# OMD_LEDS.net
KiCad netlist of a schematic drawn in Altium Designer
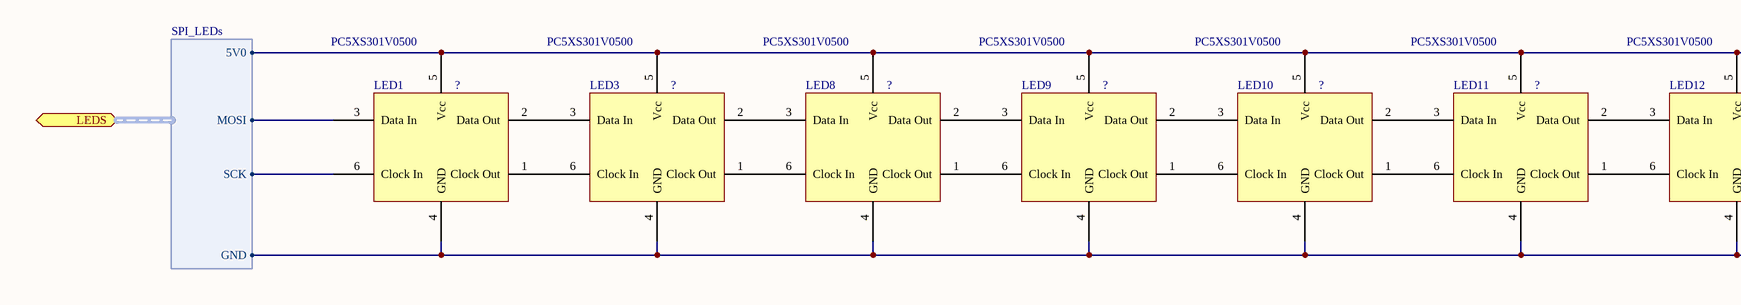
[diagram p0: OMD_LEDS.SchDoc, left]
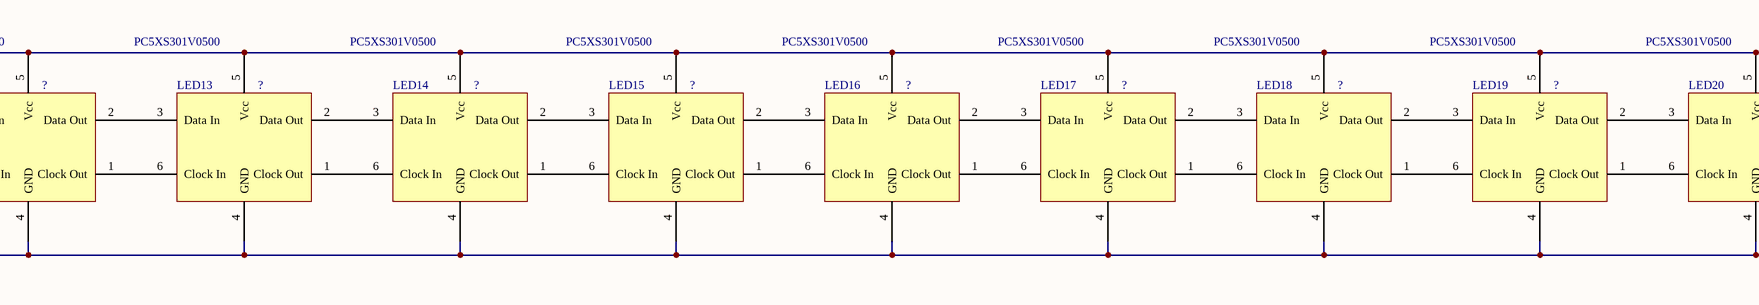
[diagram p1: OMD_LEDS.SchDoc, middle]
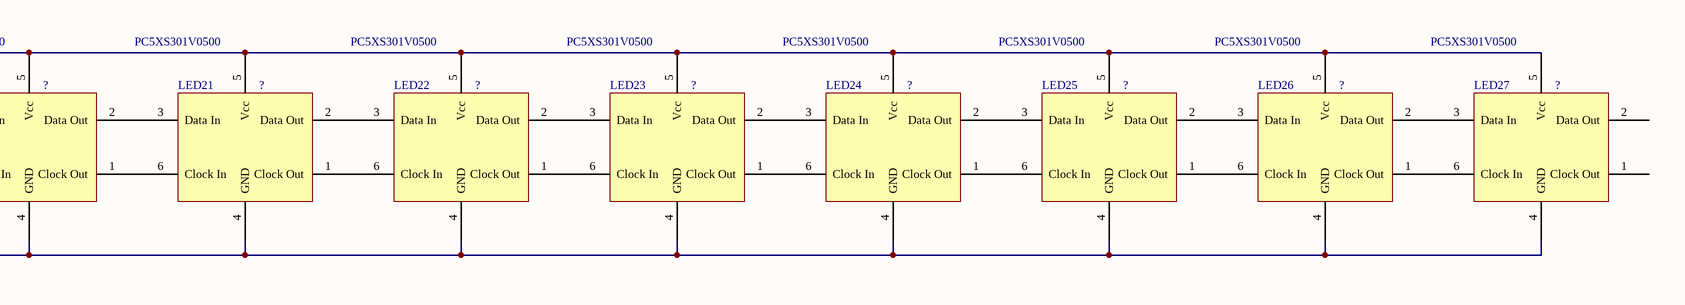
[diagram p2: OMD_LEDS.SchDoc, right]

(export (version "E")
  (design (tool "Eeschema 10.0.6"))
  (components
    (comp (ref "LED1")
      (value "?")
      (footprint "UBLED")
      (fields
        (field (name "SUPPLIER PART NUMBER 1") "PC5XS301V0500")
        (field (name "SUPPLIER 1") "jeff_chang@ubleds.com.tw")
      )
      (libsource (lib "OMD") (part "UBLED"))
    )
    (comp (ref "LED3")
      (value "?")
      (footprint "UBLED")
      (fields
        (field (name "SUPPLIER PART NUMBER 1") "PC5XS301V0500")
        (field (name "SUPPLIER 1") "jeff_chang@ubleds.com.tw")
      )
      (libsource (lib "OMD") (part "UBLED"))
    )
    (comp (ref "LED8")
      (value "?")
      (footprint "UBLED")
      (fields
        (field (name "SUPPLIER PART NUMBER 1") "PC5XS301V0500")
        (field (name "SUPPLIER 1") "jeff_chang@ubleds.com.tw")
      )
      (libsource (lib "OMD") (part "UBLED"))
    )
    (comp (ref "LED9")
      (value "?")
      (footprint "UBLED")
      (fields
        (field (name "SUPPLIER PART NUMBER 1") "PC5XS301V0500")
        (field (name "SUPPLIER 1") "jeff_chang@ubleds.com.tw")
      )
      (libsource (lib "OMD") (part "UBLED"))
    )
    (comp (ref "LED10")
      (value "?")
      (footprint "UBLED")
      (fields
        (field (name "SUPPLIER PART NUMBER 1") "PC5XS301V0500")
        (field (name "SUPPLIER 1") "jeff_chang@ubleds.com.tw")
      )
      (libsource (lib "OMD") (part "UBLED"))
    )
    (comp (ref "LED11")
      (value "?")
      (footprint "UBLED")
      (fields
        (field (name "SUPPLIER PART NUMBER 1") "PC5XS301V0500")
        (field (name "SUPPLIER 1") "jeff_chang@ubleds.com.tw")
      )
      (libsource (lib "OMD") (part "UBLED"))
    )
    (comp (ref "LED12")
      (value "?")
      (footprint "UBLED")
      (fields
        (field (name "SUPPLIER PART NUMBER 1") "PC5XS301V0500")
        (field (name "SUPPLIER 1") "jeff_chang@ubleds.com.tw")
      )
      (libsource (lib "OMD") (part "UBLED"))
    )
    (comp (ref "LED13")
      (value "?")
      (footprint "UBLED")
      (fields
        (field (name "SUPPLIER PART NUMBER 1") "PC5XS301V0500")
        (field (name "SUPPLIER 1") "jeff_chang@ubleds.com.tw")
      )
      (libsource (lib "OMD") (part "UBLED"))
    )
    (comp (ref "LED14")
      (value "?")
      (footprint "UBLED")
      (fields
        (field (name "SUPPLIER PART NUMBER 1") "PC5XS301V0500")
        (field (name "SUPPLIER 1") "jeff_chang@ubleds.com.tw")
      )
      (libsource (lib "OMD") (part "UBLED"))
    )
    (comp (ref "LED15")
      (value "?")
      (footprint "UBLED")
      (fields
        (field (name "SUPPLIER PART NUMBER 1") "PC5XS301V0500")
        (field (name "SUPPLIER 1") "jeff_chang@ubleds.com.tw")
      )
      (libsource (lib "OMD") (part "UBLED"))
    )
    (comp (ref "LED16")
      (value "?")
      (footprint "UBLED")
      (fields
        (field (name "SUPPLIER PART NUMBER 1") "PC5XS301V0500")
        (field (name "SUPPLIER 1") "jeff_chang@ubleds.com.tw")
      )
      (libsource (lib "OMD") (part "UBLED"))
    )
    (comp (ref "LED17")
      (value "?")
      (footprint "UBLED")
      (fields
        (field (name "SUPPLIER PART NUMBER 1") "PC5XS301V0500")
        (field (name "SUPPLIER 1") "jeff_chang@ubleds.com.tw")
      )
      (libsource (lib "OMD") (part "UBLED"))
    )
    (comp (ref "LED18")
      (value "?")
      (footprint "UBLED")
      (fields
        (field (name "SUPPLIER PART NUMBER 1") "PC5XS301V0500")
        (field (name "SUPPLIER 1") "jeff_chang@ubleds.com.tw")
      )
      (libsource (lib "OMD") (part "UBLED"))
    )
    (comp (ref "LED19")
      (value "?")
      (footprint "UBLED")
      (fields
        (field (name "SUPPLIER PART NUMBER 1") "PC5XS301V0500")
        (field (name "SUPPLIER 1") "jeff_chang@ubleds.com.tw")
      )
      (libsource (lib "OMD") (part "UBLED"))
    )
    (comp (ref "LED20")
      (value "?")
      (footprint "UBLED")
      (fields
        (field (name "SUPPLIER PART NUMBER 1") "PC5XS301V0500")
        (field (name "SUPPLIER 1") "jeff_chang@ubleds.com.tw")
      )
      (libsource (lib "OMD") (part "UBLED"))
    )
    (comp (ref "LED21")
      (value "?")
      (footprint "UBLED")
      (fields
        (field (name "SUPPLIER PART NUMBER 1") "PC5XS301V0500")
        (field (name "SUPPLIER 1") "jeff_chang@ubleds.com.tw")
      )
      (libsource (lib "OMD") (part "UBLED"))
    )
    (comp (ref "LED22")
      (value "?")
      (footprint "UBLED")
      (fields
        (field (name "SUPPLIER PART NUMBER 1") "PC5XS301V0500")
        (field (name "SUPPLIER 1") "jeff_chang@ubleds.com.tw")
      )
      (libsource (lib "OMD") (part "UBLED"))
    )
    (comp (ref "LED23")
      (value "?")
      (footprint "UBLED")
      (fields
        (field (name "SUPPLIER PART NUMBER 1") "PC5XS301V0500")
        (field (name "SUPPLIER 1") "jeff_chang@ubleds.com.tw")
      )
      (libsource (lib "OMD") (part "UBLED"))
    )
    (comp (ref "LED24")
      (value "?")
      (footprint "UBLED")
      (fields
        (field (name "SUPPLIER PART NUMBER 1") "PC5XS301V0500")
        (field (name "SUPPLIER 1") "jeff_chang@ubleds.com.tw")
      )
      (libsource (lib "OMD") (part "UBLED"))
    )
    (comp (ref "LED25")
      (value "?")
      (footprint "UBLED")
      (fields
        (field (name "SUPPLIER PART NUMBER 1") "PC5XS301V0500")
        (field (name "SUPPLIER 1") "jeff_chang@ubleds.com.tw")
      )
      (libsource (lib "OMD") (part "UBLED"))
    )
    (comp (ref "LED26")
      (value "?")
      (footprint "UBLED")
      (fields
        (field (name "SUPPLIER PART NUMBER 1") "PC5XS301V0500")
        (field (name "SUPPLIER 1") "jeff_chang@ubleds.com.tw")
      )
      (libsource (lib "OMD") (part "UBLED"))
    )
    (comp (ref "LED27")
      (value "?")
      (footprint "UBLED")
      (fields
        (field (name "SUPPLIER PART NUMBER 1") "PC5XS301V0500")
        (field (name "SUPPLIER 1") "jeff_chang@ubleds.com.tw")
      )
      (libsource (lib "OMD") (part "UBLED"))
    )
  )
  (nets
    (net (code "2") (name "/5V0") (class "Default")
      (node (ref "LED1") (pin "5") (pinfunction "Vcc_5") (pintype "passive"))
      (node (ref "LED10") (pin "5") (pinfunction "Vcc_5") (pintype "passive"))
      (node (ref "LED11") (pin "5") (pinfunction "Vcc_5") (pintype "passive"))
      (node (ref "LED12") (pin "5") (pinfunction "Vcc_5") (pintype "passive"))
      (node (ref "LED13") (pin "5") (pinfunction "Vcc_5") (pintype "passive"))
      (node (ref "LED14") (pin "5") (pinfunction "Vcc_5") (pintype "passive"))
      (node (ref "LED15") (pin "5") (pinfunction "Vcc_5") (pintype "passive"))
      (node (ref "LED16") (pin "5") (pinfunction "Vcc_5") (pintype "passive"))
      (node (ref "LED17") (pin "5") (pinfunction "Vcc_5") (pintype "passive"))
      (node (ref "LED18") (pin "5") (pinfunction "Vcc_5") (pintype "passive"))
      (node (ref "LED19") (pin "5") (pinfunction "Vcc_5") (pintype "passive"))
      (node (ref "LED20") (pin "5") (pinfunction "Vcc_5") (pintype "passive"))
      (node (ref "LED21") (pin "5") (pinfunction "Vcc_5") (pintype "passive"))
      (node (ref "LED22") (pin "5") (pinfunction "Vcc_5") (pintype "passive"))
      (node (ref "LED23") (pin "5") (pinfunction "Vcc_5") (pintype "passive"))
      (node (ref "LED24") (pin "5") (pinfunction "Vcc_5") (pintype "passive"))
      (node (ref "LED25") (pin "5") (pinfunction "Vcc_5") (pintype "passive"))
      (node (ref "LED26") (pin "5") (pinfunction "Vcc_5") (pintype "passive"))
      (node (ref "LED27") (pin "5") (pinfunction "Vcc_5") (pintype "passive"))
      (node (ref "LED3") (pin "5") (pinfunction "Vcc_5") (pintype "passive"))
      (node (ref "LED8") (pin "5") (pinfunction "Vcc_5") (pintype "passive"))
      (node (ref "LED9") (pin "5") (pinfunction "Vcc_5") (pintype "passive"))
    )
    (net (code "3") (name "/GND") (class "Default")
      (node (ref "LED1") (pin "4") (pinfunction "GND_4") (pintype "passive"))
      (node (ref "LED10") (pin "4") (pinfunction "GND_4") (pintype "passive"))
      (node (ref "LED11") (pin "4") (pinfunction "GND_4") (pintype "passive"))
      (node (ref "LED12") (pin "4") (pinfunction "GND_4") (pintype "passive"))
      (node (ref "LED13") (pin "4") (pinfunction "GND_4") (pintype "passive"))
      (node (ref "LED14") (pin "4") (pinfunction "GND_4") (pintype "passive"))
      (node (ref "LED15") (pin "4") (pinfunction "GND_4") (pintype "passive"))
      (node (ref "LED16") (pin "4") (pinfunction "GND_4") (pintype "passive"))
      (node (ref "LED17") (pin "4") (pinfunction "GND_4") (pintype "passive"))
      (node (ref "LED18") (pin "4") (pinfunction "GND_4") (pintype "passive"))
      (node (ref "LED19") (pin "4") (pinfunction "GND_4") (pintype "passive"))
      (node (ref "LED20") (pin "4") (pinfunction "GND_4") (pintype "passive"))
      (node (ref "LED21") (pin "4") (pinfunction "GND_4") (pintype "passive"))
      (node (ref "LED22") (pin "4") (pinfunction "GND_4") (pintype "passive"))
      (node (ref "LED23") (pin "4") (pinfunction "GND_4") (pintype "passive"))
      (node (ref "LED24") (pin "4") (pinfunction "GND_4") (pintype "passive"))
      (node (ref "LED25") (pin "4") (pinfunction "GND_4") (pintype "passive"))
      (node (ref "LED26") (pin "4") (pinfunction "GND_4") (pintype "passive"))
      (node (ref "LED27") (pin "4") (pinfunction "GND_4") (pintype "passive"))
      (node (ref "LED3") (pin "4") (pinfunction "GND_4") (pintype "passive"))
      (node (ref "LED8") (pin "4") (pinfunction "GND_4") (pintype "passive"))
      (node (ref "LED9") (pin "4") (pinfunction "GND_4") (pintype "passive"))
    )
    (net (code "4") (name "/MOSI") (class "Default")
      (node (ref "LED1") (pin "3") (pinfunction "Data_In_3") (pintype "passive"))
    )
    (net (code "5") (name "/SCK") (class "Default")
      (node (ref "LED1") (pin "6") (pinfunction "Clock_In_6") (pintype "passive"))
    )
    (net (code "7") (name "Net-(LED1-Clock_Out)") (class "Default")
      (node (ref "LED1") (pin "1") (pinfunction "Clock_Out_1") (pintype "passive"))
      (node (ref "LED3") (pin "6") (pinfunction "Clock_In_6") (pintype "passive"))
    )
    (net (code "8") (name "Net-(LED1-Data_Out)") (class "Default")
      (node (ref "LED1") (pin "2") (pinfunction "Data_Out_2") (pintype "passive"))
      (node (ref "LED3") (pin "3") (pinfunction "Data_In_3") (pintype "passive"))
    )
    (net (code "9") (name "Net-(LED3-Clock_Out)") (class "Default")
      (node (ref "LED3") (pin "1") (pinfunction "Clock_Out_1") (pintype "passive"))
      (node (ref "LED8") (pin "6") (pinfunction "Clock_In_6") (pintype "passive"))
    )
    (net (code "10") (name "Net-(LED3-Data_Out)") (class "Default")
      (node (ref "LED3") (pin "2") (pinfunction "Data_Out_2") (pintype "passive"))
      (node (ref "LED8") (pin "3") (pinfunction "Data_In_3") (pintype "passive"))
    )
    (net (code "11") (name "Net-(LED8-Clock_Out)") (class "Default")
      (node (ref "LED8") (pin "1") (pinfunction "Clock_Out_1") (pintype "passive"))
      (node (ref "LED9") (pin "6") (pinfunction "Clock_In_6") (pintype "passive"))
    )
    (net (code "12") (name "Net-(LED8-Data_Out)") (class "Default")
      (node (ref "LED8") (pin "2") (pinfunction "Data_Out_2") (pintype "passive"))
      (node (ref "LED9") (pin "3") (pinfunction "Data_In_3") (pintype "passive"))
    )
    (net (code "13") (name "Net-(LED10-Clock_In)") (class "Default")
      (node (ref "LED10") (pin "6") (pinfunction "Clock_In_6") (pintype "passive"))
      (node (ref "LED9") (pin "1") (pinfunction "Clock_Out_1") (pintype "passive"))
    )
    (net (code "14") (name "Net-(LED10-Clock_Out)") (class "Default")
      (node (ref "LED10") (pin "1") (pinfunction "Clock_Out_1") (pintype "passive"))
      (node (ref "LED11") (pin "6") (pinfunction "Clock_In_6") (pintype "passive"))
    )
    (net (code "15") (name "Net-(LED10-Data_In)") (class "Default")
      (node (ref "LED10") (pin "3") (pinfunction "Data_In_3") (pintype "passive"))
      (node (ref "LED9") (pin "2") (pinfunction "Data_Out_2") (pintype "passive"))
    )
    (net (code "16") (name "Net-(LED10-Data_Out)") (class "Default")
      (node (ref "LED10") (pin "2") (pinfunction "Data_Out_2") (pintype "passive"))
      (node (ref "LED11") (pin "3") (pinfunction "Data_In_3") (pintype "passive"))
    )
    (net (code "17") (name "Net-(LED11-Clock_Out)") (class "Default")
      (node (ref "LED11") (pin "1") (pinfunction "Clock_Out_1") (pintype "passive"))
      (node (ref "LED12") (pin "6") (pinfunction "Clock_In_6") (pintype "passive"))
    )
    (net (code "18") (name "Net-(LED11-Data_Out)") (class "Default")
      (node (ref "LED11") (pin "2") (pinfunction "Data_Out_2") (pintype "passive"))
      (node (ref "LED12") (pin "3") (pinfunction "Data_In_3") (pintype "passive"))
    )
    (net (code "19") (name "Net-(LED12-Clock_Out)") (class "Default")
      (node (ref "LED12") (pin "1") (pinfunction "Clock_Out_1") (pintype "passive"))
      (node (ref "LED13") (pin "6") (pinfunction "Clock_In_6") (pintype "passive"))
    )
    (net (code "20") (name "Net-(LED12-Data_Out)") (class "Default")
      (node (ref "LED12") (pin "2") (pinfunction "Data_Out_2") (pintype "passive"))
      (node (ref "LED13") (pin "3") (pinfunction "Data_In_3") (pintype "passive"))
    )
    (net (code "21") (name "Net-(LED13-Clock_Out)") (class "Default")
      (node (ref "LED13") (pin "1") (pinfunction "Clock_Out_1") (pintype "passive"))
      (node (ref "LED14") (pin "6") (pinfunction "Clock_In_6") (pintype "passive"))
    )
    (net (code "22") (name "Net-(LED13-Data_Out)") (class "Default")
      (node (ref "LED13") (pin "2") (pinfunction "Data_Out_2") (pintype "passive"))
      (node (ref "LED14") (pin "3") (pinfunction "Data_In_3") (pintype "passive"))
    )
    (net (code "23") (name "Net-(LED14-Clock_Out)") (class "Default")
      (node (ref "LED14") (pin "1") (pinfunction "Clock_Out_1") (pintype "passive"))
      (node (ref "LED15") (pin "6") (pinfunction "Clock_In_6") (pintype "passive"))
    )
    (net (code "24") (name "Net-(LED14-Data_Out)") (class "Default")
      (node (ref "LED14") (pin "2") (pinfunction "Data_Out_2") (pintype "passive"))
      (node (ref "LED15") (pin "3") (pinfunction "Data_In_3") (pintype "passive"))
    )
    (net (code "25") (name "Net-(LED15-Clock_Out)") (class "Default")
      (node (ref "LED15") (pin "1") (pinfunction "Clock_Out_1") (pintype "passive"))
      (node (ref "LED16") (pin "6") (pinfunction "Clock_In_6") (pintype "passive"))
    )
    (net (code "26") (name "Net-(LED15-Data_Out)") (class "Default")
      (node (ref "LED15") (pin "2") (pinfunction "Data_Out_2") (pintype "passive"))
      (node (ref "LED16") (pin "3") (pinfunction "Data_In_3") (pintype "passive"))
    )
    (net (code "27") (name "Net-(LED16-Clock_Out)") (class "Default")
      (node (ref "LED16") (pin "1") (pinfunction "Clock_Out_1") (pintype "passive"))
      (node (ref "LED17") (pin "6") (pinfunction "Clock_In_6") (pintype "passive"))
    )
    (net (code "28") (name "Net-(LED16-Data_Out)") (class "Default")
      (node (ref "LED16") (pin "2") (pinfunction "Data_Out_2") (pintype "passive"))
      (node (ref "LED17") (pin "3") (pinfunction "Data_In_3") (pintype "passive"))
    )
    (net (code "29") (name "Net-(LED17-Clock_Out)") (class "Default")
      (node (ref "LED17") (pin "1") (pinfunction "Clock_Out_1") (pintype "passive"))
      (node (ref "LED18") (pin "6") (pinfunction "Clock_In_6") (pintype "passive"))
    )
    (net (code "30") (name "Net-(LED17-Data_Out)") (class "Default")
      (node (ref "LED17") (pin "2") (pinfunction "Data_Out_2") (pintype "passive"))
      (node (ref "LED18") (pin "3") (pinfunction "Data_In_3") (pintype "passive"))
    )
    (net (code "31") (name "Net-(LED18-Clock_Out)") (class "Default")
      (node (ref "LED18") (pin "1") (pinfunction "Clock_Out_1") (pintype "passive"))
      (node (ref "LED19") (pin "6") (pinfunction "Clock_In_6") (pintype "passive"))
    )
    (net (code "32") (name "Net-(LED18-Data_Out)") (class "Default")
      (node (ref "LED18") (pin "2") (pinfunction "Data_Out_2") (pintype "passive"))
      (node (ref "LED19") (pin "3") (pinfunction "Data_In_3") (pintype "passive"))
    )
    (net (code "33") (name "Net-(LED19-Clock_Out)") (class "Default")
      (node (ref "LED19") (pin "1") (pinfunction "Clock_Out_1") (pintype "passive"))
      (node (ref "LED20") (pin "6") (pinfunction "Clock_In_6") (pintype "passive"))
    )
    (net (code "34") (name "Net-(LED19-Data_Out)") (class "Default")
      (node (ref "LED19") (pin "2") (pinfunction "Data_Out_2") (pintype "passive"))
      (node (ref "LED20") (pin "3") (pinfunction "Data_In_3") (pintype "passive"))
    )
    (net (code "35") (name "Net-(LED20-Clock_Out)") (class "Default")
      (node (ref "LED20") (pin "1") (pinfunction "Clock_Out_1") (pintype "passive"))
      (node (ref "LED21") (pin "6") (pinfunction "Clock_In_6") (pintype "passive"))
    )
    (net (code "36") (name "Net-(LED20-Data_Out)") (class "Default")
      (node (ref "LED20") (pin "2") (pinfunction "Data_Out_2") (pintype "passive"))
      (node (ref "LED21") (pin "3") (pinfunction "Data_In_3") (pintype "passive"))
    )
    (net (code "37") (name "Net-(LED21-Clock_Out)") (class "Default")
      (node (ref "LED21") (pin "1") (pinfunction "Clock_Out_1") (pintype "passive"))
      (node (ref "LED22") (pin "6") (pinfunction "Clock_In_6") (pintype "passive"))
    )
    (net (code "38") (name "Net-(LED21-Data_Out)") (class "Default")
      (node (ref "LED21") (pin "2") (pinfunction "Data_Out_2") (pintype "passive"))
      (node (ref "LED22") (pin "3") (pinfunction "Data_In_3") (pintype "passive"))
    )
    (net (code "39") (name "Net-(LED22-Clock_Out)") (class "Default")
      (node (ref "LED22") (pin "1") (pinfunction "Clock_Out_1") (pintype "passive"))
      (node (ref "LED23") (pin "6") (pinfunction "Clock_In_6") (pintype "passive"))
    )
    (net (code "40") (name "Net-(LED22-Data_Out)") (class "Default")
      (node (ref "LED22") (pin "2") (pinfunction "Data_Out_2") (pintype "passive"))
      (node (ref "LED23") (pin "3") (pinfunction "Data_In_3") (pintype "passive"))
    )
    (net (code "41") (name "Net-(LED23-Clock_Out)") (class "Default")
      (node (ref "LED23") (pin "1") (pinfunction "Clock_Out_1") (pintype "passive"))
      (node (ref "LED24") (pin "6") (pinfunction "Clock_In_6") (pintype "passive"))
    )
    (net (code "42") (name "Net-(LED23-Data_Out)") (class "Default")
      (node (ref "LED23") (pin "2") (pinfunction "Data_Out_2") (pintype "passive"))
      (node (ref "LED24") (pin "3") (pinfunction "Data_In_3") (pintype "passive"))
    )
    (net (code "43") (name "Net-(LED24-Clock_Out)") (class "Default")
      (node (ref "LED24") (pin "1") (pinfunction "Clock_Out_1") (pintype "passive"))
      (node (ref "LED25") (pin "6") (pinfunction "Clock_In_6") (pintype "passive"))
    )
    (net (code "44") (name "Net-(LED24-Data_Out)") (class "Default")
      (node (ref "LED24") (pin "2") (pinfunction "Data_Out_2") (pintype "passive"))
      (node (ref "LED25") (pin "3") (pinfunction "Data_In_3") (pintype "passive"))
    )
    (net (code "45") (name "Net-(LED25-Clock_Out)") (class "Default")
      (node (ref "LED25") (pin "1") (pinfunction "Clock_Out_1") (pintype "passive"))
      (node (ref "LED26") (pin "6") (pinfunction "Clock_In_6") (pintype "passive"))
    )
    (net (code "46") (name "Net-(LED25-Data_Out)") (class "Default")
      (node (ref "LED25") (pin "2") (pinfunction "Data_Out_2") (pintype "passive"))
      (node (ref "LED26") (pin "3") (pinfunction "Data_In_3") (pintype "passive"))
    )
    (net (code "47") (name "Net-(LED26-Clock_Out)") (class "Default")
      (node (ref "LED26") (pin "1") (pinfunction "Clock_Out_1") (pintype "passive"))
      (node (ref "LED27") (pin "6") (pinfunction "Clock_In_6") (pintype "passive"))
    )
    (net (code "48") (name "Net-(LED26-Data_Out)") (class "Default")
      (node (ref "LED26") (pin "2") (pinfunction "Data_Out_2") (pintype "passive"))
      (node (ref "LED27") (pin "3") (pinfunction "Data_In_3") (pintype "passive"))
    )
    (net (code "49") (name "unconnected-(LED27-Clock_Out-Pad1)") (class "Default")
      (node (ref "LED27") (pin "1") (pinfunction "Clock_Out_1") (pintype "passive"))
    )
    (net (code "50") (name "unconnected-(LED27-Data_Out-Pad2)") (class "Default")
      (node (ref "LED27") (pin "2") (pinfunction "Data_Out_2") (pintype "passive"))
    )
  )
)
